# controller.net
KiCad netlist of a schematic drawn in Altium Designer
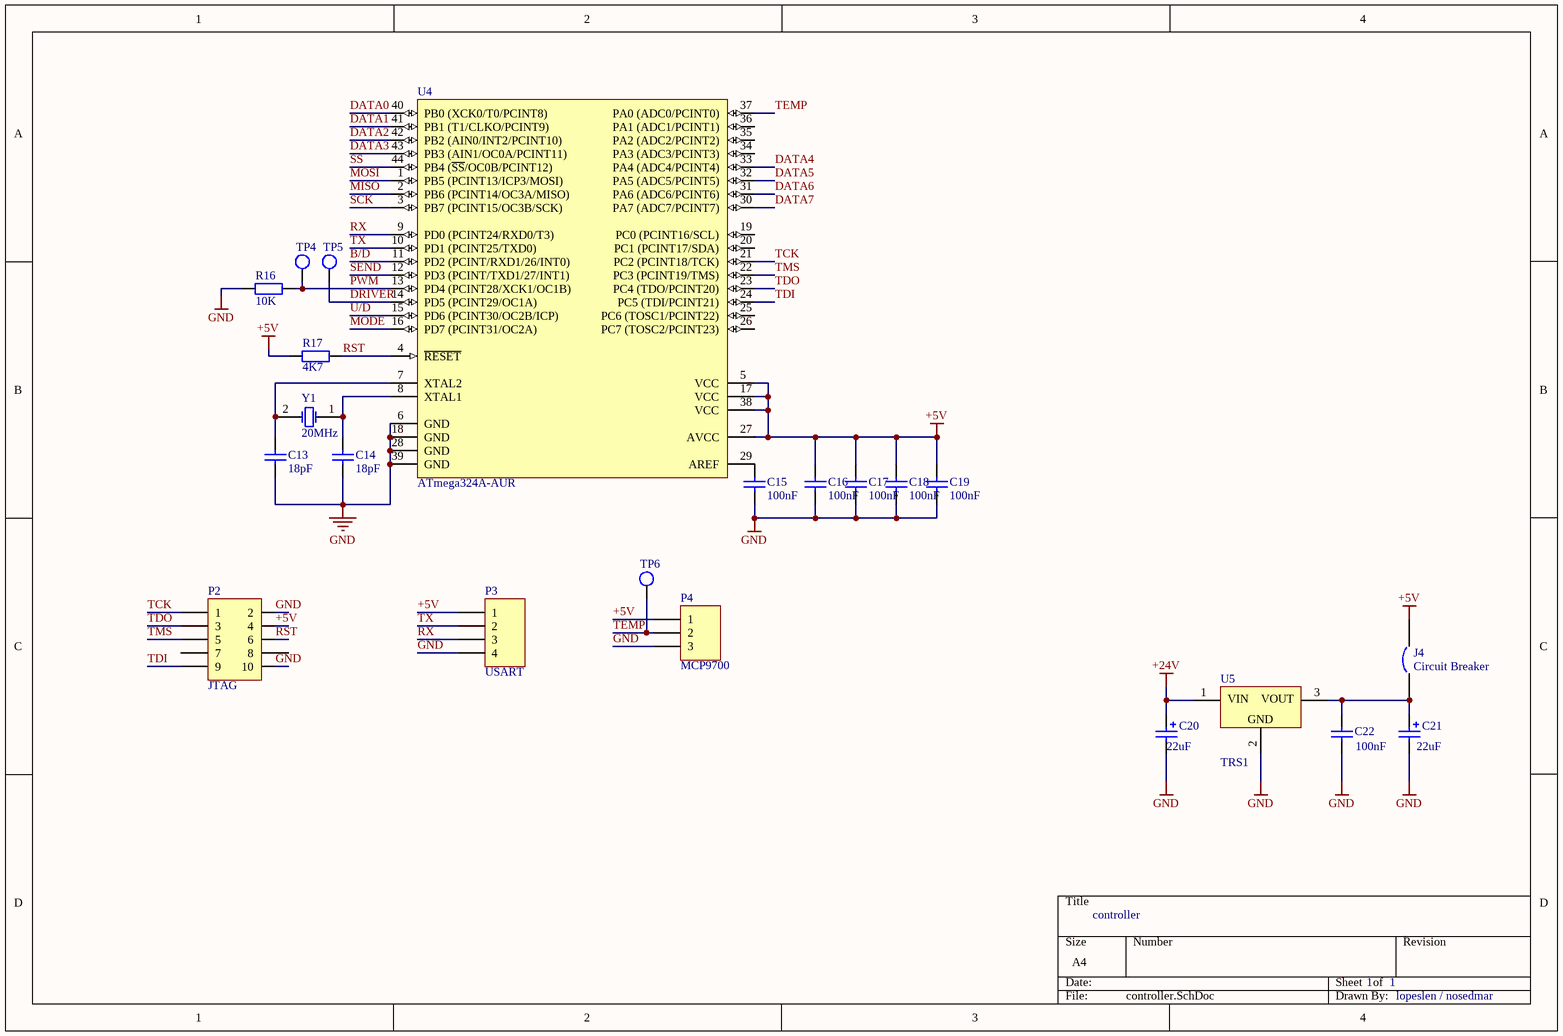
[diagram p0: controller.SchDoc]

(export (version "E")
  (design (tool "Eeschema 10.0.6"))
  (components
    (comp (ref "C13")
      (value "18pF")
      (footprint "6-0805_M")
      (description "Capacitor")
      (fields (field (name "Comment") "Cap") (field (name "PUBLISHER") "Altium Limited"))
      (libsource (lib "Miscellaneous Devices") (part "Cap"))
    )
    (comp (ref "C14")
      (value "18pF")
      (footprint "6-0805_M")
      (description "Capacitor")
      (fields (field (name "Comment") "Cap") (field (name "PUBLISHER") "Altium Limited"))
      (libsource (lib "Miscellaneous Devices") (part "Cap"))
    )
    (comp (ref "C15")
      (value "100nF")
      (footprint "6-0805_M")
      (description "Capacitor")
      (fields (field (name "Comment") "Cap") (field (name "PUBLISHER") "Altium Limited"))
      (libsource (lib "Miscellaneous Devices") (part "Cap"))
    )
    (comp (ref "C16")
      (value "100nF")
      (footprint "6-0805_M")
      (description "Capacitor")
      (fields (field (name "Comment") "Cap") (field (name "PUBLISHER") "Altium Limited"))
      (libsource (lib "Miscellaneous Devices") (part "Cap"))
    )
    (comp (ref "C17")
      (value "100nF")
      (footprint "6-0805_M")
      (description "Capacitor")
      (fields (field (name "Comment") "Cap") (field (name "PUBLISHER") "Altium Limited"))
      (libsource (lib "Miscellaneous Devices") (part "Cap"))
    )
    (comp (ref "C18")
      (value "100nF")
      (footprint "6-0805_M")
      (description "Capacitor")
      (fields (field (name "Comment") "Cap") (field (name "PUBLISHER") "Altium Limited"))
      (libsource (lib "Miscellaneous Devices") (part "Cap"))
    )
    (comp (ref "C19")
      (value "100nF")
      (footprint "6-0805_M")
      (description "Capacitor")
      (fields (field (name "Comment") "Cap") (field (name "PUBLISHER") "Altium Limited"))
      (libsource (lib "Miscellaneous Devices") (part "Cap"))
    )
    (comp (ref "C20")
      (value "22uF")
      (footprint "EEEFK1H")
      (description "Polarized Capacitor (Axial)")
      (fields (field (name "Comment") "Cap Pol2") (field (name "PUBLISHER") "Altium Limited"))
      (libsource (lib "Miscellaneous Devices") (part "Cap Pol2"))
    )
    (comp (ref "C21")
      (value "22uF")
      (footprint "EEEFK1H")
      (description "Polarized Capacitor (Axial)")
      (fields (field (name "Comment") "Cap Pol2") (field (name "PUBLISHER") "Altium Limited"))
      (libsource (lib "Miscellaneous Devices") (part "Cap Pol2"))
    )
    (comp (ref "C22")
      (value "100nF")
      (footprint "6-0805_M")
      (description "Capacitor")
      (fields (field (name "Comment") "Cap") (field (name "PUBLISHER") "Altium Limited"))
      (libsource (lib "Miscellaneous Devices") (part "Cap"))
    )
    (comp (ref "J4")
      (value "Circuit Breaker")
      (footprint "SOLDER_JUMPER_24mil")
      (fields (field (name "PUBLISHER") "Altium Limited"))
      (libsource (lib "Miscellaneous Devices") (part "Circuit Breaker"))
    )
    (comp (ref "P2")
      (value "JTAG")
      (footprint "HDR2X5")
      (description "Header, 5-Pin, Dual row")
      (fields (field (name "PUBLISHER") "Altium Limited"))
      (libsource (lib "Miscellaneous Connectors") (part "Header 5X2"))
    )
    (comp (ref "P3")
      (value "USART")
      (footprint "HDR1X4")
      (description "Header, 4-Pin")
      (fields (field (name "PUBLISHER") "Altium Limited"))
      (libsource (lib "Miscellaneous Connectors") (part "Header 4"))
    )
    (comp (ref "P4")
      (value "MCP9700")
      (footprint "HDR1X3")
      (description "Header, 3-Pin")
      (fields (field (name "PUBLISHER") "Altium Limited"))
      (libsource (lib "Miscellaneous Connectors") (part "Header 3"))
    )
    (comp (ref "R16")
      (value "10K")
      (footprint "6-0805_M")
      (description "Resistor")
      (fields (field (name "Comment") "Res2") (field (name "PUBLISHER") "Altium Limited"))
      (libsource (lib "Miscellaneous Devices") (part "Res2"))
    )
    (comp (ref "R17")
      (value "4K7")
      (footprint "6-0805_M")
      (description "Resistor")
      (fields (field (name "Comment") "Res2") (field (name "PUBLISHER") "Altium Limited"))
      (libsource (lib "Miscellaneous Devices") (part "Res2"))
    )
    (comp (ref "TP4")
      (value "TestPoint")
      (footprint "MEASUREMENT_POINT")
      (description "Testpoint")
      (libsource (lib "clusterlib") (part "TestPoint"))
    )
    (comp (ref "TP5")
      (value "TestPoint")
      (footprint "MEASUREMENT_POINT")
      (description "Testpoint")
      (libsource (lib "clusterlib") (part "TestPoint"))
    )
    (comp (ref "TP6")
      (value "TestPoint")
      (footprint "MEASUREMENT_POINT")
      (description "Testpoint")
      (libsource (lib "clusterlib") (part "TestPoint"))
    )
    (comp (ref "U4")
      (value "ATmega324A-AUR")
      (footprint "44A_N")
      (libsource (lib "Atmel Microcontroller megaAVR") (part "ATmega324A-AUR"))
    )
    (comp (ref "U5")
      (value "TRS1")
      (footprint "TSR1-2450")
      (description "TSR1-2450 DC/DC Step-Down Converter")
      (libsource (lib "clusterlib") (part "TSR1-2450"))
    )
    (comp (ref "Y1")
      (value "20MHz")
      (footprint "CRYSTAL")
      (description "Crystal Oscillator")
      (fields (field (name "PUBLISHER") "Altium Limited"))
      (libsource (lib "Miscellaneous Devices") (part "XTAL"))
    )
  )
  (nets
    (net (code "1") (name "+5V") (class "Default")
      (node (ref "C16") (pin "2") (pinfunction "2_2") (pintype "passive"))
      (node (ref "C17") (pin "2") (pinfunction "2_2") (pintype "passive"))
      (node (ref "C18") (pin "2") (pinfunction "2_2") (pintype "passive"))
      (node (ref "C19") (pin "2") (pinfunction "2_2") (pintype "passive"))
      (node (ref "J4") (pin "2") (pinfunction "2_2") (pintype "passive"))
      (node (ref "P2") (pin "4") (pinfunction "4_4") (pintype "passive"))
      (node (ref "P3") (pin "1") (pinfunction "1_1") (pintype "passive"))
      (node (ref "P4") (pin "1") (pinfunction "1_1") (pintype "passive"))
      (node (ref "R17") (pin "2") (pinfunction "2_2") (pintype "passive"))
      (node (ref "U4") (pin "17") (pinfunction "VCC_17") (pintype "power_in"))
      (node (ref "U4") (pin "27") (pinfunction "AVCC_27") (pintype "power_in"))
      (node (ref "U4") (pin "38") (pinfunction "VCC_38") (pintype "power_in"))
      (node (ref "U4") (pin "5") (pinfunction "VCC_5") (pintype "power_in"))
    )
    (net (code "2") (name "+24V") (class "Default")
      (node (ref "C20") (pin "1") (pinfunction "1_1") (pintype "passive"))
      (node (ref "U5") (pin "1") (pinfunction "+VIN_1") (pintype "passive"))
    )
    (net (code "3") (name "/DATA0") (class "Default")
      (node (ref "U4") (pin "40") (pinfunction "PB0_(XCK0/T0/PCINT8)_40") (pintype "bidirectional"))
    )
    (net (code "4") (name "/DATA1") (class "Default")
      (node (ref "U4") (pin "41") (pinfunction "PB1_(T1/CLKO/PCINT9)_41") (pintype "bidirectional"))
    )
    (net (code "5") (name "/DATA2") (class "Default")
      (node (ref "U4") (pin "42") (pinfunction "PB2_(AIN0/INT2/PCINT10)_42") (pintype "bidirectional"))
    )
    (net (code "6") (name "/DATA3") (class "Default")
      (node (ref "U4") (pin "43") (pinfunction "PB3_(AIN1/OC0A/PCINT11)_43") (pintype "bidirectional"))
    )
    (net (code "7") (name "/DATA4") (class "Default")
      (node (ref "U4") (pin "33") (pinfunction "PA4_(ADC4/PCINT4)_33") (pintype "bidirectional"))
    )
    (net (code "8") (name "/DATA5") (class "Default")
      (node (ref "U4") (pin "32") (pinfunction "PA5_(ADC5/PCINT5)_32") (pintype "bidirectional"))
    )
    (net (code "9") (name "/DATA6") (class "Default")
      (node (ref "U4") (pin "31") (pinfunction "PA6_(ADC6/PCINT6)_31") (pintype "bidirectional"))
    )
    (net (code "10") (name "/DATA7") (class "Default")
      (node (ref "U4") (pin "30") (pinfunction "PA7_(ADC7/PCINT7)_30") (pintype "bidirectional"))
    )
    (net (code "11") (name "/DRIVER") (class "Default")
      (node (ref "TP5") (pin "1") (pinfunction "1_1") (pintype "passive"))
      (node (ref "U4") (pin "14") (pinfunction "PD5_(PCINT29/OC1A)_14") (pintype "bidirectional"))
    )
    (net (code "12") (name "/MISO") (class "Default")
      (node (ref "U4") (pin "2") (pinfunction "PB6_(PCINT14/OC3A/MISO)_2") (pintype "bidirectional"))
    )
    (net (code "13") (name "/MODE") (class "Default")
      (node (ref "U4") (pin "16") (pinfunction "PD7_(PCINT31/OC2A)_16") (pintype "bidirectional"))
    )
    (net (code "14") (name "/MOSI") (class "Default")
      (node (ref "U4") (pin "1") (pinfunction "PB5_(PCINT13/ICP3/MOSI)_1") (pintype "bidirectional"))
    )
    (net (code "15") (name "/PWM") (class "Default")
      (node (ref "R16") (pin "1") (pinfunction "1_1") (pintype "passive"))
      (node (ref "TP4") (pin "1") (pinfunction "1_1") (pintype "passive"))
      (node (ref "U4") (pin "13") (pinfunction "PD4_(PCINT28/XCK1/OC1B)_13") (pintype "bidirectional"))
    )
    (net (code "16") (name "/RST") (class "Default")
      (node (ref "P2") (pin "6") (pinfunction "6_6") (pintype "passive"))
      (node (ref "R17") (pin "1") (pinfunction "1_1") (pintype "passive"))
      (node (ref "U4") (pin "4") (pinfunction "~{RESET}_4") (pintype "input"))
    )
    (net (code "17") (name "/RX") (class "Default")
      (node (ref "P3") (pin "3") (pinfunction "3_3") (pintype "passive"))
      (node (ref "U4") (pin "9") (pinfunction "PD0_(PCINT24/RXD0/T3)_9") (pintype "bidirectional"))
    )
    (net (code "18") (name "/SCK") (class "Default")
      (node (ref "U4") (pin "3") (pinfunction "PB7_(PCINT15/OC3B/SCK)_3") (pintype "bidirectional"))
    )
    (net (code "19") (name "/SEND") (class "Default")
      (node (ref "U4") (pin "12") (pinfunction "PD3_(PCINT/TXD1/27/INT1)_12") (pintype "bidirectional"))
    )
    (net (code "20") (name "/TCK") (class "Default")
      (node (ref "P2") (pin "1") (pinfunction "1_1") (pintype "passive"))
      (node (ref "U4") (pin "21") (pinfunction "PC2_(PCINT18/TCK)_21") (pintype "bidirectional"))
    )
    (net (code "21") (name "/TDI") (class "Default")
      (node (ref "P2") (pin "9") (pinfunction "9_9") (pintype "passive"))
      (node (ref "U4") (pin "24") (pinfunction "PC5_(TDI/PCINT21)_24") (pintype "bidirectional"))
    )
    (net (code "22") (name "/TDO") (class "Default")
      (node (ref "P2") (pin "3") (pinfunction "3_3") (pintype "passive"))
      (node (ref "U4") (pin "23") (pinfunction "PC4_(TDO/PCINT20)_23") (pintype "bidirectional"))
    )
    (net (code "23") (name "/TEMP") (class "Default")
      (node (ref "P4") (pin "2") (pinfunction "2_2") (pintype "passive"))
      (node (ref "TP6") (pin "1") (pinfunction "1_1") (pintype "passive"))
      (node (ref "U4") (pin "37") (pinfunction "PA0_(ADC0/PCINT0)_37") (pintype "bidirectional"))
    )
    (net (code "24") (name "/TMS") (class "Default")
      (node (ref "P2") (pin "5") (pinfunction "5_5") (pintype "passive"))
      (node (ref "U4") (pin "22") (pinfunction "PC3_(PCINT19/TMS)_22") (pintype "bidirectional"))
    )
    (net (code "25") (name "/TX") (class "Default")
      (node (ref "P3") (pin "2") (pinfunction "2_2") (pintype "passive"))
      (node (ref "U4") (pin "10") (pinfunction "PD1_(PCINT25/TXD0)_10") (pintype "bidirectional"))
    )
    (net (code "26") (name "/U{slash}D") (class "Default")
      (node (ref "U4") (pin "15") (pinfunction "PD6_(PCINT30/OC2B/ICP)_15") (pintype "bidirectional"))
    )
    (net (code "27") (name "/~{B}{slash}D") (class "Default")
      (node (ref "U4") (pin "11") (pinfunction "PD2_(PCINT/RXD1/26/INT0)_11") (pintype "bidirectional"))
    )
    (net (code "28") (name "/~{SS}") (class "Default")
      (node (ref "U4") (pin "44") (pinfunction "PB4_(~{SS}/OC0B/PCINT12)_44") (pintype "bidirectional"))
    )
    (net (code "29") (name "GND") (class "Default")
      (node (ref "C13") (pin "1") (pinfunction "1_1") (pintype "passive"))
      (node (ref "C14") (pin "1") (pinfunction "1_1") (pintype "passive"))
      (node (ref "C15") (pin "1") (pinfunction "1_1") (pintype "passive"))
      (node (ref "C16") (pin "1") (pinfunction "1_1") (pintype "passive"))
      (node (ref "C17") (pin "1") (pinfunction "1_1") (pintype "passive"))
      (node (ref "C18") (pin "1") (pinfunction "1_1") (pintype "passive"))
      (node (ref "C19") (pin "1") (pinfunction "1_1") (pintype "passive"))
      (node (ref "C20") (pin "2") (pinfunction "2_2") (pintype "passive"))
      (node (ref "C21") (pin "2") (pinfunction "2_2") (pintype "passive"))
      (node (ref "C22") (pin "1") (pinfunction "1_1") (pintype "passive"))
      (node (ref "P2") (pin "10") (pinfunction "10_10") (pintype "passive"))
      (node (ref "P2") (pin "2") (pinfunction "2_2") (pintype "passive"))
      (node (ref "P3") (pin "4") (pinfunction "4_4") (pintype "passive"))
      (node (ref "P4") (pin "3") (pinfunction "3_3") (pintype "passive"))
      (node (ref "R16") (pin "2") (pinfunction "2_2") (pintype "passive"))
      (node (ref "U4") (pin "18") (pinfunction "GND_18") (pintype "power_in"))
      (node (ref "U4") (pin "28") (pinfunction "GND_28") (pintype "power_in"))
      (node (ref "U4") (pin "39") (pinfunction "GND_39") (pintype "power_in"))
      (node (ref "U4") (pin "6") (pinfunction "GND_6") (pintype "power_in"))
      (node (ref "U5") (pin "2") (pinfunction "GND_2") (pintype "passive"))
    )
    (net (code "30") (name "Net-(U4-AREF)") (class "Default")
      (node (ref "C15") (pin "2") (pinfunction "2_2") (pintype "passive"))
      (node (ref "U4") (pin "29") (pinfunction "AREF_29") (pintype "power_in"))
    )
    (net (code "31") (name "Net-(U4-XTAL1)") (class "Default")
      (node (ref "C14") (pin "2") (pinfunction "2_2") (pintype "passive"))
      (node (ref "U4") (pin "8") (pinfunction "XTAL1_8") (pintype "passive"))
      (node (ref "Y1") (pin "1") (pinfunction "OSC1_1") (pintype "passive"))
    )
    (net (code "32") (name "Net-(U4-XTAL2)") (class "Default")
      (node (ref "C13") (pin "2") (pinfunction "2_2") (pintype "passive"))
      (node (ref "U4") (pin "7") (pinfunction "XTAL2_7") (pintype "passive"))
      (node (ref "Y1") (pin "2") (pinfunction "OSC2_2") (pintype "passive"))
    )
    (net (code "33") (name "Net-(U5-+VOUT)") (class "Default")
      (node (ref "C21") (pin "1") (pinfunction "1_1") (pintype "passive"))
      (node (ref "C22") (pin "2") (pinfunction "2_2") (pintype "passive"))
      (node (ref "J4") (pin "1") (pinfunction "1_1") (pintype "passive"))
      (node (ref "U5") (pin "3") (pinfunction "+VOUT_3") (pintype "passive"))
    )
    (net (code "34") (name "unconnected-(P2-Pad7)") (class "Default")
      (node (ref "P2") (pin "7") (pinfunction "7_7") (pintype "passive"))
    )
    (net (code "35") (name "unconnected-(P2-Pad8)") (class "Default")
      (node (ref "P2") (pin "8") (pinfunction "8_8") (pintype "passive"))
    )
    (net (code "36") (name "unconnected-(U4-PA1_(ADC1{slash}PCINT1)-Pad36)") (class "Default")
      (node (ref "U4") (pin "36") (pinfunction "PA1_(ADC1/PCINT1)_36") (pintype "bidirectional"))
    )
    (net (code "37") (name "unconnected-(U4-PA2_(ADC2{slash}PCINT2)-Pad35)") (class "Default")
      (node (ref "U4") (pin "35") (pinfunction "PA2_(ADC2/PCINT2)_35") (pintype "bidirectional"))
    )
    (net (code "38") (name "unconnected-(U4-PA3_(ADC3{slash}PCINT3)-Pad34)") (class "Default")
      (node (ref "U4") (pin "34") (pinfunction "PA3_(ADC3/PCINT3)_34") (pintype "bidirectional"))
    )
    (net (code "39") (name "unconnected-(U4-PC0_(PCINT16{slash}SCL)-Pad19)") (class "Default")
      (node (ref "U4") (pin "19") (pinfunction "PC0_(PCINT16/SCL)_19") (pintype "bidirectional"))
    )
    (net (code "40") (name "unconnected-(U4-PC1_(PCINT17{slash}SDA)-Pad20)") (class "Default")
      (node (ref "U4") (pin "20") (pinfunction "PC1_(PCINT17/SDA)_20") (pintype "bidirectional"))
    )
    (net (code "41") (name "unconnected-(U4-PC6_(TOSC1{slash}PCINT22)-Pad25)") (class "Default")
      (node (ref "U4") (pin "25") (pinfunction "PC6_(TOSC1/PCINT22)_25") (pintype "bidirectional"))
    )
    (net (code "42") (name "unconnected-(U4-PC7_(TOSC2{slash}PCINT23)-Pad26)") (class "Default")
      (node (ref "U4") (pin "26") (pinfunction "PC7_(TOSC2/PCINT23)_26") (pintype "bidirectional"))
    )
  )
)
